# 9_-CAMERA_POWER_CONTROLLER.net
KiCad netlist of a schematic drawn in Altium Designer
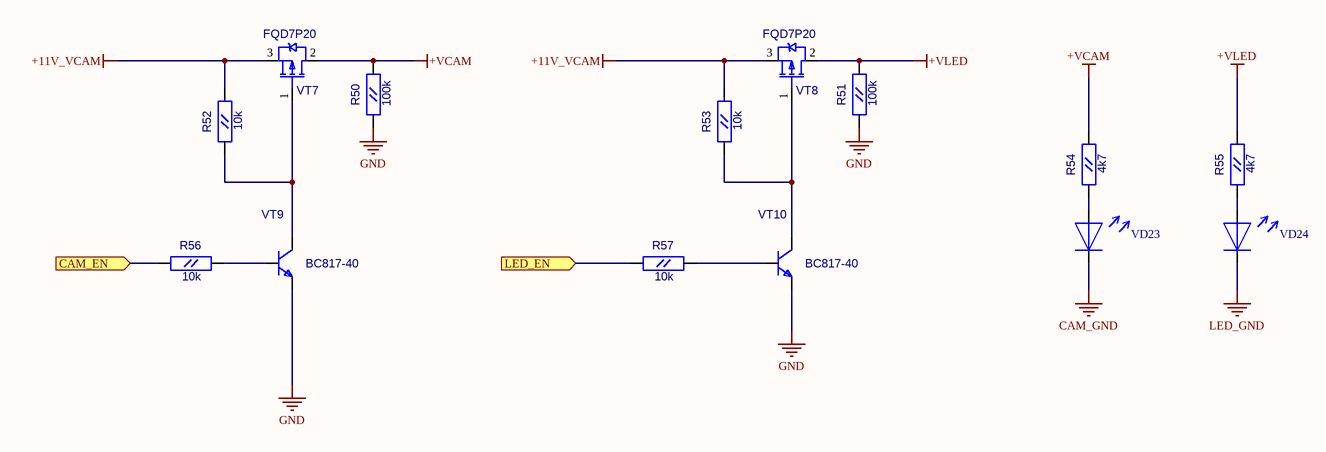
[diagram p0: [9]-CAMERA_POWER_CONTROLLER.SchDoc]

(export (version "E")
  (design (tool "Eeschema 10.0.6"))
  (components
    (comp (ref "R50")
      (value "100k")
      (footprint "RC0603")
      (description "RC0603")
      (libsource (lib "fizik_lib") (part "RC0603"))
    )
    (comp (ref "R51")
      (value "100k")
      (footprint "RC0603")
      (description "RC0603")
      (libsource (lib "fizik_lib") (part "RC0603"))
    )
    (comp (ref "R52")
      (value "10k")
      (footprint "RC0603")
      (description "RC0603")
      (libsource (lib "fizik_lib") (part "RC0603"))
    )
    (comp (ref "R53")
      (value "10k")
      (footprint "RC0603")
      (description "RC0603")
      (libsource (lib "fizik_lib") (part "RC0603"))
    )
    (comp (ref "R54")
      (value "4k7")
      (footprint "RC0603")
      (description "RC0603")
      (libsource (lib "gprs_modem_2") (part "RC0603"))
    )
    (comp (ref "R55")
      (value "4k7")
      (footprint "RC0603")
      (description "RC0603")
      (libsource (lib "gprs_modem_2") (part "RC0603"))
    )
    (comp (ref "R56")
      (value "10k")
      (footprint "RC0603")
      (description "RC0603")
      (libsource (lib "fizik_lib") (part "RC0603"))
    )
    (comp (ref "R57")
      (value "10k")
      (footprint "RC0603")
      (description "RC0603")
      (libsource (lib "fizik_lib") (part "RC0603"))
    )
    (comp (ref "VD23")
      (value "LED_0805")
      (footprint "LED0805")
      (libsource (lib "gprs_modem_2") (part "LED_0805"))
    )
    (comp (ref "VD24")
      (value "LED_0805")
      (footprint "LED0805")
      (libsource (lib "gprs_modem_2") (part "LED_0805"))
    )
    (comp (ref "VT7")
      (value "FQD7P20")
      (footprint "D-PAK(TO-252AA)")
      (description "HEXFET Power MOSFET")
      (libsource (lib "gprs_modem_2") (part "IRFR9220"))
    )
    (comp (ref "VT8")
      (value "FQD7P20")
      (footprint "D-PAK(TO-252AA)")
      (description "HEXFET Power MOSFET")
      (libsource (lib "gprs_modem_2") (part "IRFR9220"))
    )
    (comp (ref "VT9")
      (value "BC817-40")
      (footprint "SOT-23(123)")
      (description "NPN 500ma transistor")
      (libsource (lib "fizik_lib") (part "BC846BLT1"))
    )
    (comp (ref "VT10")
      (value "BC817-40")
      (footprint "SOT-23(123)")
      (description "NPN 500ma transistor")
      (libsource (lib "fizik_lib") (part "BC846BLT1"))
    )
  )
  (nets
    (net (code "1") (name "+11V_VCAM") (class "Default")
      (node (ref "R52") (pin "2") (pinfunction "B_2") (pintype "passive"))
      (node (ref "R53") (pin "2") (pinfunction "B_2") (pintype "passive"))
      (node (ref "VT7") (pin "3") (pinfunction "S_3") (pintype "passive"))
      (node (ref "VT8") (pin "3") (pinfunction "S_3") (pintype "passive"))
    )
    (net (code "2") (name "+VCAM") (class "Default")
      (node (ref "R50") (pin "2") (pinfunction "B_2") (pintype "passive"))
      (node (ref "R54") (pin "2") (pinfunction "B_2") (pintype "passive"))
      (node (ref "VT7") (pin "2") (pinfunction "D_2") (pintype "passive"))
    )
    (net (code "3") (name "+VLED") (class "Default")
      (node (ref "R51") (pin "2") (pinfunction "B_2") (pintype "passive"))
      (node (ref "R55") (pin "2") (pinfunction "B_2") (pintype "passive"))
      (node (ref "VT8") (pin "2") (pinfunction "D_2") (pintype "passive"))
    )
    (net (code "4") (name "/CAM_EN") (class "Default")
      (node (ref "R56") (pin "1") (pinfunction "A_1") (pintype "passive"))
    )
    (net (code "5") (name "/LED_EN") (class "Default")
      (node (ref "R57") (pin "1") (pinfunction "A_1") (pintype "passive"))
    )
    (net (code "6") (name "CAM_GND") (class "Default") (node (ref "VD23") (pin "2") (pintype "passive")))
    (net (code "7") (name "GND") (class "Default")
      (node (ref "R50") (pin "1") (pinfunction "A_1") (pintype "passive"))
      (node (ref "R51") (pin "1") (pinfunction "A_1") (pintype "passive"))
      (node (ref "VT10") (pin "2") (pinfunction "E_2") (pintype "passive"))
      (node (ref "VT9") (pin "2") (pinfunction "E_2") (pintype "passive"))
    )
    (net (code "8") (name "LED_GND") (class "Default") (node (ref "VD24") (pin "2") (pintype "passive")))
    (net (code "9") (name "Net-(R52-A)") (class "Default")
      (node (ref "R52") (pin "1") (pinfunction "A_1") (pintype "passive"))
      (node (ref "VT7") (pin "1") (pinfunction "G_1") (pintype "passive"))
      (node (ref "VT9") (pin "3") (pinfunction "C_3") (pintype "passive"))
    )
    (net (code "10") (name "Net-(R53-A)") (class "Default")
      (node (ref "R53") (pin "1") (pinfunction "A_1") (pintype "passive"))
      (node (ref "VT10") (pin "3") (pinfunction "C_3") (pintype "passive"))
      (node (ref "VT8") (pin "1") (pinfunction "G_1") (pintype "passive"))
    )
    (net (code "11") (name "Net-(R54-A)") (class "Default")
      (node (ref "R54") (pin "1") (pinfunction "A_1") (pintype "passive"))
      (node (ref "VD23") (pin "1") (pintype "passive"))
    )
    (net (code "12") (name "Net-(R55-A)") (class "Default")
      (node (ref "R55") (pin "1") (pinfunction "A_1") (pintype "passive"))
      (node (ref "VD24") (pin "1") (pintype "passive"))
    )
    (net (code "13") (name "Net-(R56-B)") (class "Default")
      (node (ref "R56") (pin "2") (pinfunction "B_2") (pintype "passive"))
      (node (ref "VT9") (pin "1") (pinfunction "B_1") (pintype "passive"))
    )
    (net (code "14") (name "Net-(R57-B)") (class "Default")
      (node (ref "R57") (pin "2") (pinfunction "B_2") (pintype "passive"))
      (node (ref "VT10") (pin "1") (pinfunction "B_1") (pintype "passive"))
    )
  )
)
